# Sip_And_Puff_Analog_Switch.net
KiCad netlist of a schematic drawn in EAGLE
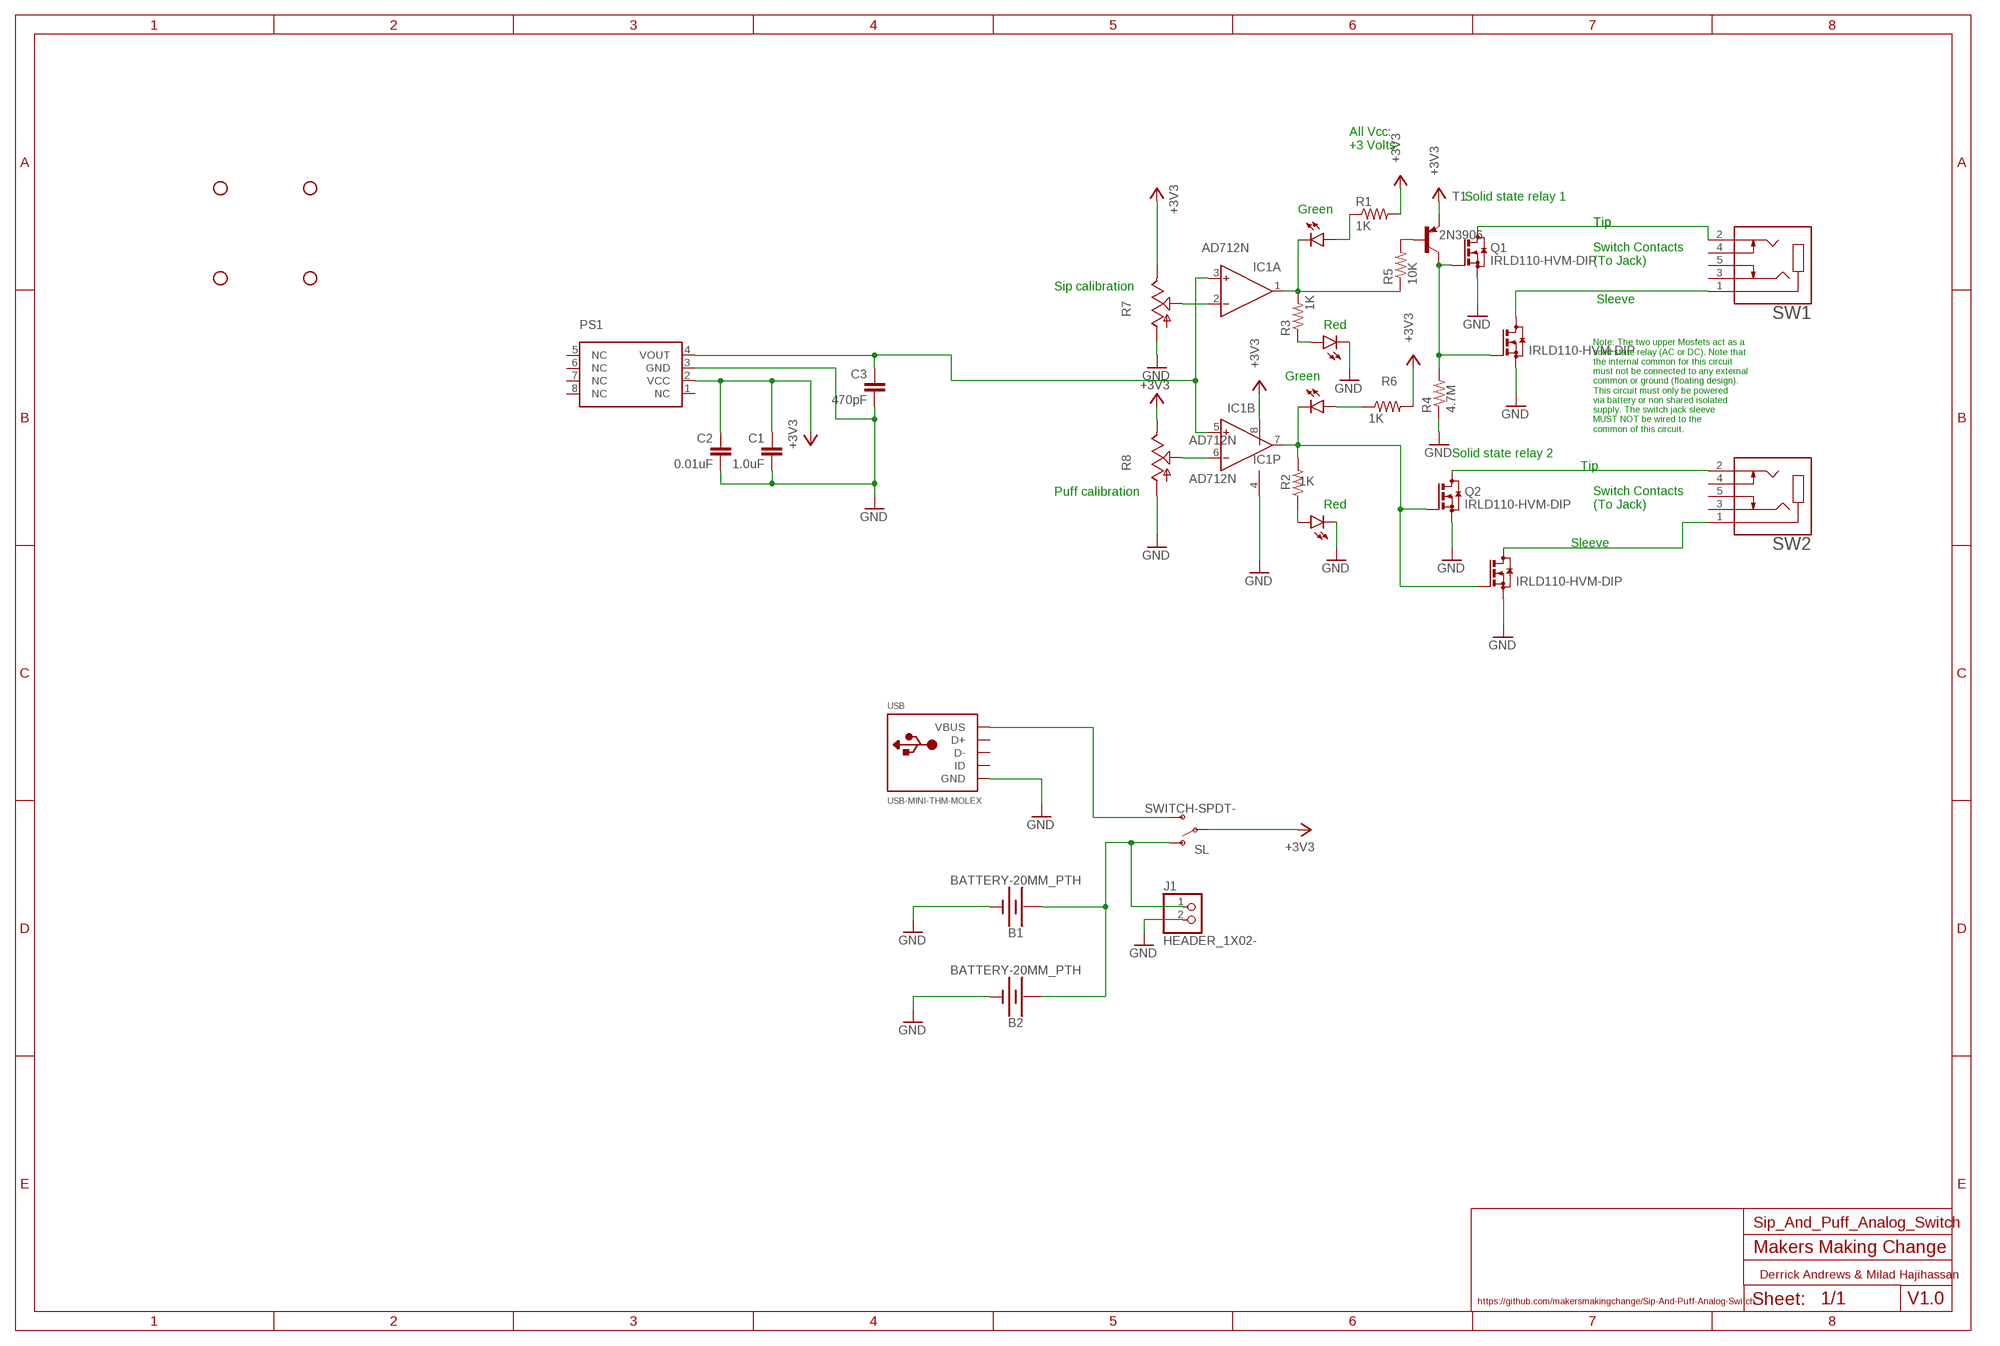
[diagram p0: schematic, sheet 1]

(export (version "E")
  (design (tool "Eeschema 10.0.6"))
  (components
    (comp (ref "B1")
      (value "BATTERY-20MM_PTH")
      (footprint "eagle-import:BATTCOM_20MM_PTH")
      (libsource (lib "eagle-import") (part "BATTERY-20MM_PTH"))
    )
    (comp (ref "B2")
      (value "BATTERY-20MM_PTH")
      (footprint "eagle-import:BATTCOM_20MM_PTH")
      (libsource (lib "eagle-import") (part "BATTERY-20MM_PTH"))
    )
    (comp (ref "C1")
      (value "1.0uF")
      (footprint "eagle-import:CAP-PTH-SMALL-KIT")
      (libsource (lib "eagle-import") (part "CAPACITOR-EU-"))
    )
    (comp (ref "C2")
      (value "0.01uF")
      (footprint "eagle-import:CAP-PTH-SMALL-KIT")
      (libsource (lib "eagle-import") (part "CAPACITOR-EU-"))
    )
    (comp (ref "C3")
      (value "470pF")
      (footprint "eagle-import:CAP-PTH-SMALL-KIT")
      (libsource (lib "eagle-import") (part "CAPACITOR-EU-"))
    )
    (comp (ref "IC1")
      (value "AD712N")
      (footprint "eagle-import:DIL08")
      (fields (field (name "MF") "ALTERA CORPORATION") (field (name "MPN") "AD712JNZ"))
      (libsource (lib "eagle-import") (part "AD712N"))
    )
    (comp (ref "J1")
      (value "HEADER_1X02-")
      (footprint "eagle-import:1X02")
      (libsource (lib "eagle-import") (part "HEADER_1X02-"))
    )
    (comp (ref "LED1")
      (value "LED5MM-RED")
      (footprint "eagle-import:LED_5MM_RED")
      (libsource (lib "eagle-import") (part "LED5MM-RED"))
    )
    (comp (ref "LED2")
      (value "LED5MM-RED")
      (footprint "eagle-import:LED_5MM_RED")
      (libsource (lib "eagle-import") (part "LED5MM-RED"))
    )
    (comp (ref "LED3")
      (value "LED5MM-GREEN")
      (footprint "eagle-import:LED_5MM_GREEN")
      (libsource (lib "eagle-import") (part "LED5MM-GREEN"))
    )
    (comp (ref "LED4")
      (value "LED5MM-GREEN")
      (footprint "eagle-import:LED_5MM_GREEN")
      (libsource (lib "eagle-import") (part "LED5MM-GREEN"))
    )
    (comp (ref "PS1")
      (value "MPX-")
      (footprint "eagle-import:MXP_SOP8")
      (libsource (lib "eagle-import") (part "MPX-"))
    )
    (comp (ref "Q1")
      (value "IRLD110-HVM-DIP")
      (footprint "eagle-import:HVM-DIP")
      (libsource (lib "eagle-import") (part "IRLD110-HVM-DIP"))
    )
    (comp (ref "Q2")
      (value "IRLD110-HVM-DIP")
      (footprint "eagle-import:HVM-DIP")
      (libsource (lib "eagle-import") (part "IRLD110-HVM-DIP"))
    )
    (comp (ref "Q3")
      (value "IRLD110-HVM-DIP")
      (footprint "eagle-import:HVM-DIP")
      (libsource (lib "eagle-import") (part "IRLD110-HVM-DIP"))
    )
    (comp (ref "Q4")
      (value "IRLD110-HVM-DIP")
      (footprint "eagle-import:HVM-DIP")
      (libsource (lib "eagle-import") (part "IRLD110-HVM-DIP"))
    )
    (comp (ref "R1")
      (value "1K")
      (footprint "eagle-import:RESISTOR_0207_7")
      (libsource (lib "eagle-import") (part "RESISTOR-US-0207/7"))
    )
    (comp (ref "R2")
      (value "1K")
      (footprint "eagle-import:RESISTOR_0207_7")
      (libsource (lib "eagle-import") (part "RESISTOR-US-0207/7"))
    )
    (comp (ref "R3")
      (value "1K")
      (footprint "eagle-import:RESISTOR_0207_7")
      (libsource (lib "eagle-import") (part "RESISTOR-US-0207/7"))
    )
    (comp (ref "R4")
      (value "4.7M")
      (footprint "eagle-import:RESISTOR_0207_7")
      (libsource (lib "eagle-import") (part "RESISTOR-US-0207/7"))
    )
    (comp (ref "R5")
      (value "10K")
      (footprint "eagle-import:RESISTOR_0207_7")
      (libsource (lib "eagle-import") (part "RESISTOR-US-0207/7"))
    )
    (comp (ref "R6")
      (value "1K")
      (footprint "eagle-import:RESISTOR_0207_7")
      (libsource (lib "eagle-import") (part "RESISTOR-US-0207/7"))
    )
    (comp (ref "R7")
      (value "TRIM-3386C")
      (footprint "eagle-import:3386C")
      (libsource (lib "eagle-import") (part "TRIM-3386C"))
    )
    (comp (ref "R8")
      (value "TRIM-3386C")
      (footprint "eagle-import:3386C")
      (libsource (lib "eagle-import") (part "TRIM-3386C"))
    )
    (comp (ref "SL")
      (value "SWITCH-SPDT-")
      (footprint "eagle-import:SPDT-RA")
      (libsource (lib "eagle-import") (part "SWITCH-SPDT-"))
    )
    (comp (ref "STANDOFF1")
      (value "STAND-OFF-")
      (footprint "eagle-import:STAND-OFF")
      (libsource (lib "eagle-import") (part "STAND-OFF-"))
    )
    (comp (ref "STANDOFF2")
      (value "STAND-OFF-")
      (footprint "eagle-import:STAND-OFF")
      (libsource (lib "eagle-import") (part "STAND-OFF-"))
    )
    (comp (ref "STANDOFF3")
      (value "STAND-OFF-")
      (footprint "eagle-import:STAND-OFF")
      (libsource (lib "eagle-import") (part "STAND-OFF-"))
    )
    (comp (ref "STANDOFF4")
      (value "STAND-OFF-")
      (footprint "eagle-import:STAND-OFF")
      (libsource (lib "eagle-import") (part "STAND-OFF-"))
    )
    (comp (ref "SW1")
      (value "CUI_SJ1-3535NGSJ1-3535NG")
      (footprint "eagle-import:CUI_SJ1-3535NG")
      (libsource (lib "eagle-import") (part "CUI_SJ1-3535NGSJ1-3535NG"))
    )
    (comp (ref "SW2")
      (value "CUI_SJ1-3535NGSJ1-3535NG")
      (footprint "eagle-import:CUI_SJ1-3535NG")
      (libsource (lib "eagle-import") (part "CUI_SJ1-3535NGSJ1-3535NG"))
    )
    (comp (ref "T1")
      (value "2N3906")
      (footprint "eagle-import:TO92-EBC")
      (libsource (lib "eagle-import") (part "2N3906"))
    )
    (comp (ref "USB")
      (value "USB-MINI-THM-MOLEX")
      (footprint "eagle-import:USB-MINIB-THM-MOLEX")
      (libsource (lib "eagle-import") (part "USB-MINI-THM-MOLEX"))
    )
  )
  (nets
    (net (code "1") (name "+3V3") (class "Default")
      (node (ref "C1") (pin "1") (pinfunction "1_1") (pintype "passive"))
      (node (ref "C2") (pin "1") (pinfunction "1_1") (pintype "passive"))
      (node (ref "IC1") (pin "8") (pinfunction "V+_8") (pintype "power_in"))
      (node (ref "PS1") (pin "2") (pinfunction "VCC_2") (pintype "power_in"))
      (node (ref "R1") (pin "2") (pinfunction "2_2") (pintype "passive"))
      (node (ref "R6") (pin "2") (pinfunction "2_2") (pintype "passive"))
      (node (ref "R7") (pin "E") (pinfunction "E_E") (pintype "passive"))
      (node (ref "R8") (pin "E") (pinfunction "E_E") (pintype "passive"))
      (node (ref "SL") (pin "2") (pinfunction "P_2") (pintype "passive"))
      (node (ref "T1") (pin "E") (pinfunction "E_E") (pintype "passive"))
    )
    (net (code "2") (name "GND") (class "Default")
      (node (ref "B1") (pin "-") (pinfunction "-_-") (pintype "power_in"))
      (node (ref "B2") (pin "-") (pinfunction "-_-") (pintype "power_in"))
      (node (ref "C1") (pin "2") (pinfunction "2_2") (pintype "passive"))
      (node (ref "C2") (pin "2") (pinfunction "2_2") (pintype "passive"))
      (node (ref "C3") (pin "2") (pinfunction "2_2") (pintype "passive"))
      (node (ref "IC1") (pin "4") (pinfunction "V-_4") (pintype "power_in"))
      (node (ref "J1") (pin "2") (pinfunction "2_2") (pintype "passive"))
      (node (ref "LED1") (pin "K") (pinfunction "C_K") (pintype "passive"))
      (node (ref "LED2") (pin "K") (pinfunction "C_K") (pintype "passive"))
      (node (ref "PS1") (pin "3") (pinfunction "GND_3") (pintype "power_in"))
      (node (ref "Q1") (pin "2") (pinfunction "S_2") (pintype "passive"))
      (node (ref "Q2") (pin "2") (pinfunction "S_2") (pintype "passive"))
      (node (ref "Q3") (pin "2") (pinfunction "S_2") (pintype "passive"))
      (node (ref "Q4") (pin "2") (pinfunction "S_2") (pintype "passive"))
      (node (ref "R4") (pin "1") (pinfunction "1_1") (pintype "passive"))
      (node (ref "R7") (pin "A") (pinfunction "A_A") (pintype "passive"))
      (node (ref "R8") (pin "A") (pinfunction "A_A") (pintype "passive"))
      (node (ref "USB") (pin "GND") (pinfunction "GND_GND") (pintype "power_in"))
    )
    (net (code "3") (name "Net-(IC1A-IN+)") (class "Default")
      (node (ref "C3") (pin "1") (pinfunction "1_1") (pintype "passive"))
      (node (ref "IC1") (pin "3") (pinfunction "IN+_3") (pintype "input"))
      (node (ref "IC1") (pin "5") (pinfunction "IN+_5") (pintype "input"))
      (node (ref "PS1") (pin "4") (pinfunction "VOUT_4") (pintype "output"))
    )
    (net (code "4") (name "Net-(IC1A-IN-)") (class "Default")
      (node (ref "IC1") (pin "2") (pinfunction "IN-_2") (pintype "input"))
      (node (ref "R7") (pin "S") (pinfunction "S_S") (pintype "passive"))
    )
    (net (code "5") (name "Net-(IC1A-OUT)") (class "Default")
      (node (ref "IC1") (pin "1") (pinfunction "OUT_1") (pintype "output"))
      (node (ref "LED3") (pin "K") (pinfunction "C_K") (pintype "passive"))
      (node (ref "R3") (pin "2") (pinfunction "2_2") (pintype "passive"))
      (node (ref "R5") (pin "1") (pinfunction "1_1") (pintype "passive"))
    )
    (net (code "6") (name "Net-(IC1B-IN-)") (class "Default")
      (node (ref "IC1") (pin "6") (pinfunction "IN-_6") (pintype "input"))
      (node (ref "R8") (pin "S") (pinfunction "S_S") (pintype "passive"))
    )
    (net (code "7") (name "Net-(IC1B-OUT)") (class "Default")
      (node (ref "IC1") (pin "7") (pinfunction "OUT_7") (pintype "output"))
      (node (ref "LED4") (pin "K") (pinfunction "C_K") (pintype "passive"))
      (node (ref "Q2") (pin "1") (pinfunction "G_1") (pintype "passive"))
      (node (ref "Q4") (pin "1") (pinfunction "G_1") (pintype "passive"))
      (node (ref "R2") (pin "2") (pinfunction "2_2") (pintype "passive"))
    )
    (net (code "8") (name "Net-(LED1-PadA)") (class "Default")
      (node (ref "LED1") (pin "A") (pinfunction "A_A") (pintype "passive"))
      (node (ref "R3") (pin "1") (pinfunction "1_1") (pintype "passive"))
    )
    (net (code "9") (name "Net-(LED2-PadA)") (class "Default")
      (node (ref "LED2") (pin "A") (pinfunction "A_A") (pintype "passive"))
      (node (ref "R2") (pin "1") (pinfunction "1_1") (pintype "passive"))
    )
    (net (code "10") (name "Net-(LED3-PadA)") (class "Default")
      (node (ref "LED3") (pin "A") (pinfunction "A_A") (pintype "passive"))
      (node (ref "R1") (pin "1") (pinfunction "1_1") (pintype "passive"))
    )
    (net (code "11") (name "Net-(LED4-PadA)") (class "Default")
      (node (ref "LED4") (pin "A") (pinfunction "A_A") (pintype "passive"))
      (node (ref "R6") (pin "1") (pinfunction "1_1") (pintype "passive"))
    )
    (net (code "12") (name "Net-(Q1-D)") (class "Default")
      (node (ref "Q1") (pin "3") (pinfunction "D_3") (pintype "passive"))
      (node (ref "SW1") (pin "2") (pinfunction "2_2") (pintype "passive"))
    )
    (net (code "13") (name "Net-(Q1-G)") (class "Default")
      (node (ref "Q1") (pin "1") (pinfunction "G_1") (pintype "passive"))
      (node (ref "Q3") (pin "1") (pinfunction "G_1") (pintype "passive"))
      (node (ref "R4") (pin "2") (pinfunction "2_2") (pintype "passive"))
      (node (ref "T1") (pin "C") (pinfunction "C_C") (pintype "passive"))
    )
    (net (code "14") (name "Net-(Q2-D)") (class "Default")
      (node (ref "Q2") (pin "3") (pinfunction "D_3") (pintype "passive"))
      (node (ref "SW2") (pin "2") (pinfunction "2_2") (pintype "passive"))
    )
    (net (code "15") (name "Net-(Q3-D)") (class "Default")
      (node (ref "Q3") (pin "3") (pinfunction "D_3") (pintype "passive"))
      (node (ref "SW1") (pin "1") (pinfunction "1_1") (pintype "passive"))
    )
    (net (code "16") (name "Net-(Q4-D)") (class "Default")
      (node (ref "Q4") (pin "3") (pinfunction "D_3") (pintype "passive"))
      (node (ref "SW2") (pin "1") (pinfunction "1_1") (pintype "passive"))
    )
    (net (code "17") (name "Net-(R5-Pad2)") (class "Default")
      (node (ref "R5") (pin "2") (pinfunction "2_2") (pintype "passive"))
      (node (ref "T1") (pin "B") (pinfunction "B_B") (pintype "passive"))
    )
    (net (code "18") (name "Net-(SL-O)") (class "Default")
      (node (ref "B1") (pin "+") (pinfunction "+_+") (pintype "power_in"))
      (node (ref "B2") (pin "+") (pinfunction "+_+") (pintype "power_in"))
      (node (ref "J1") (pin "1") (pinfunction "1_1") (pintype "passive"))
      (node (ref "SL") (pin "1") (pinfunction "O_1") (pintype "passive"))
    )
    (net (code "19") (name "Net-(SL-S)") (class "Default")
      (node (ref "SL") (pin "3") (pinfunction "S_3") (pintype "passive"))
      (node (ref "USB") (pin "VBUS") (pinfunction "VBUS_VBUS") (pintype "power_in"))
    )
    (net (code "20") (name "unconnected-(PS1-NC-Pad1)") (class "Default")
      (node (ref "PS1") (pin "1") (pinfunction "NC_1") (pintype "no_connect"))
    )
    (net (code "21") (name "unconnected-(PS1-NC-Pad5)") (class "Default")
      (node (ref "PS1") (pin "5") (pinfunction "NC_5") (pintype "no_connect"))
    )
    (net (code "22") (name "unconnected-(PS1-NC-Pad6)") (class "Default")
      (node (ref "PS1") (pin "6") (pinfunction "NC_6") (pintype "no_connect"))
    )
    (net (code "23") (name "unconnected-(PS1-NC-Pad7)") (class "Default")
      (node (ref "PS1") (pin "7") (pinfunction "NC_7") (pintype "no_connect"))
    )
    (net (code "24") (name "unconnected-(PS1-NC-Pad8)") (class "Default")
      (node (ref "PS1") (pin "8") (pinfunction "NC_8") (pintype "no_connect"))
    )
    (net (code "25") (name "unconnected-(SW1-Pad3)") (class "Default")
      (node (ref "SW1") (pin "3") (pinfunction "3_3") (pintype "passive"))
    )
    (net (code "26") (name "unconnected-(SW1-Pad4)") (class "Default")
      (node (ref "SW1") (pin "4") (pinfunction "4_4") (pintype "passive"))
    )
    (net (code "27") (name "unconnected-(SW1-Pad5)") (class "Default")
      (node (ref "SW1") (pin "5") (pinfunction "5_5") (pintype "passive"))
    )
    (net (code "28") (name "unconnected-(SW2-Pad3)") (class "Default")
      (node (ref "SW2") (pin "3") (pinfunction "3_3") (pintype "passive"))
    )
    (net (code "29") (name "unconnected-(SW2-Pad4)") (class "Default")
      (node (ref "SW2") (pin "4") (pinfunction "4_4") (pintype "passive"))
    )
    (net (code "30") (name "unconnected-(SW2-Pad5)") (class "Default")
      (node (ref "SW2") (pin "5") (pinfunction "5_5") (pintype "passive"))
    )
    (net (code "31") (name "unconnected-(USB-PadD+)") (class "Default")
      (node (ref "USB") (pin "D+") (pinfunction "D+_D+") (pintype "bidirectional"))
    )
    (net (code "32") (name "unconnected-(USB-PadD-)") (class "Default")
      (node (ref "USB") (pin "D-") (pinfunction "D-_D-") (pintype "bidirectional"))
    )
    (net (code "33") (name "unconnected-(USB-PadID)") (class "Default")
      (node (ref "USB") (pin "ID") (pinfunction "ID_ID") (pintype "bidirectional"))
    )
  )
)
